# Qwiic_RFID_Tag_X01.net
KiCad netlist of a schematic drawn in EAGLE
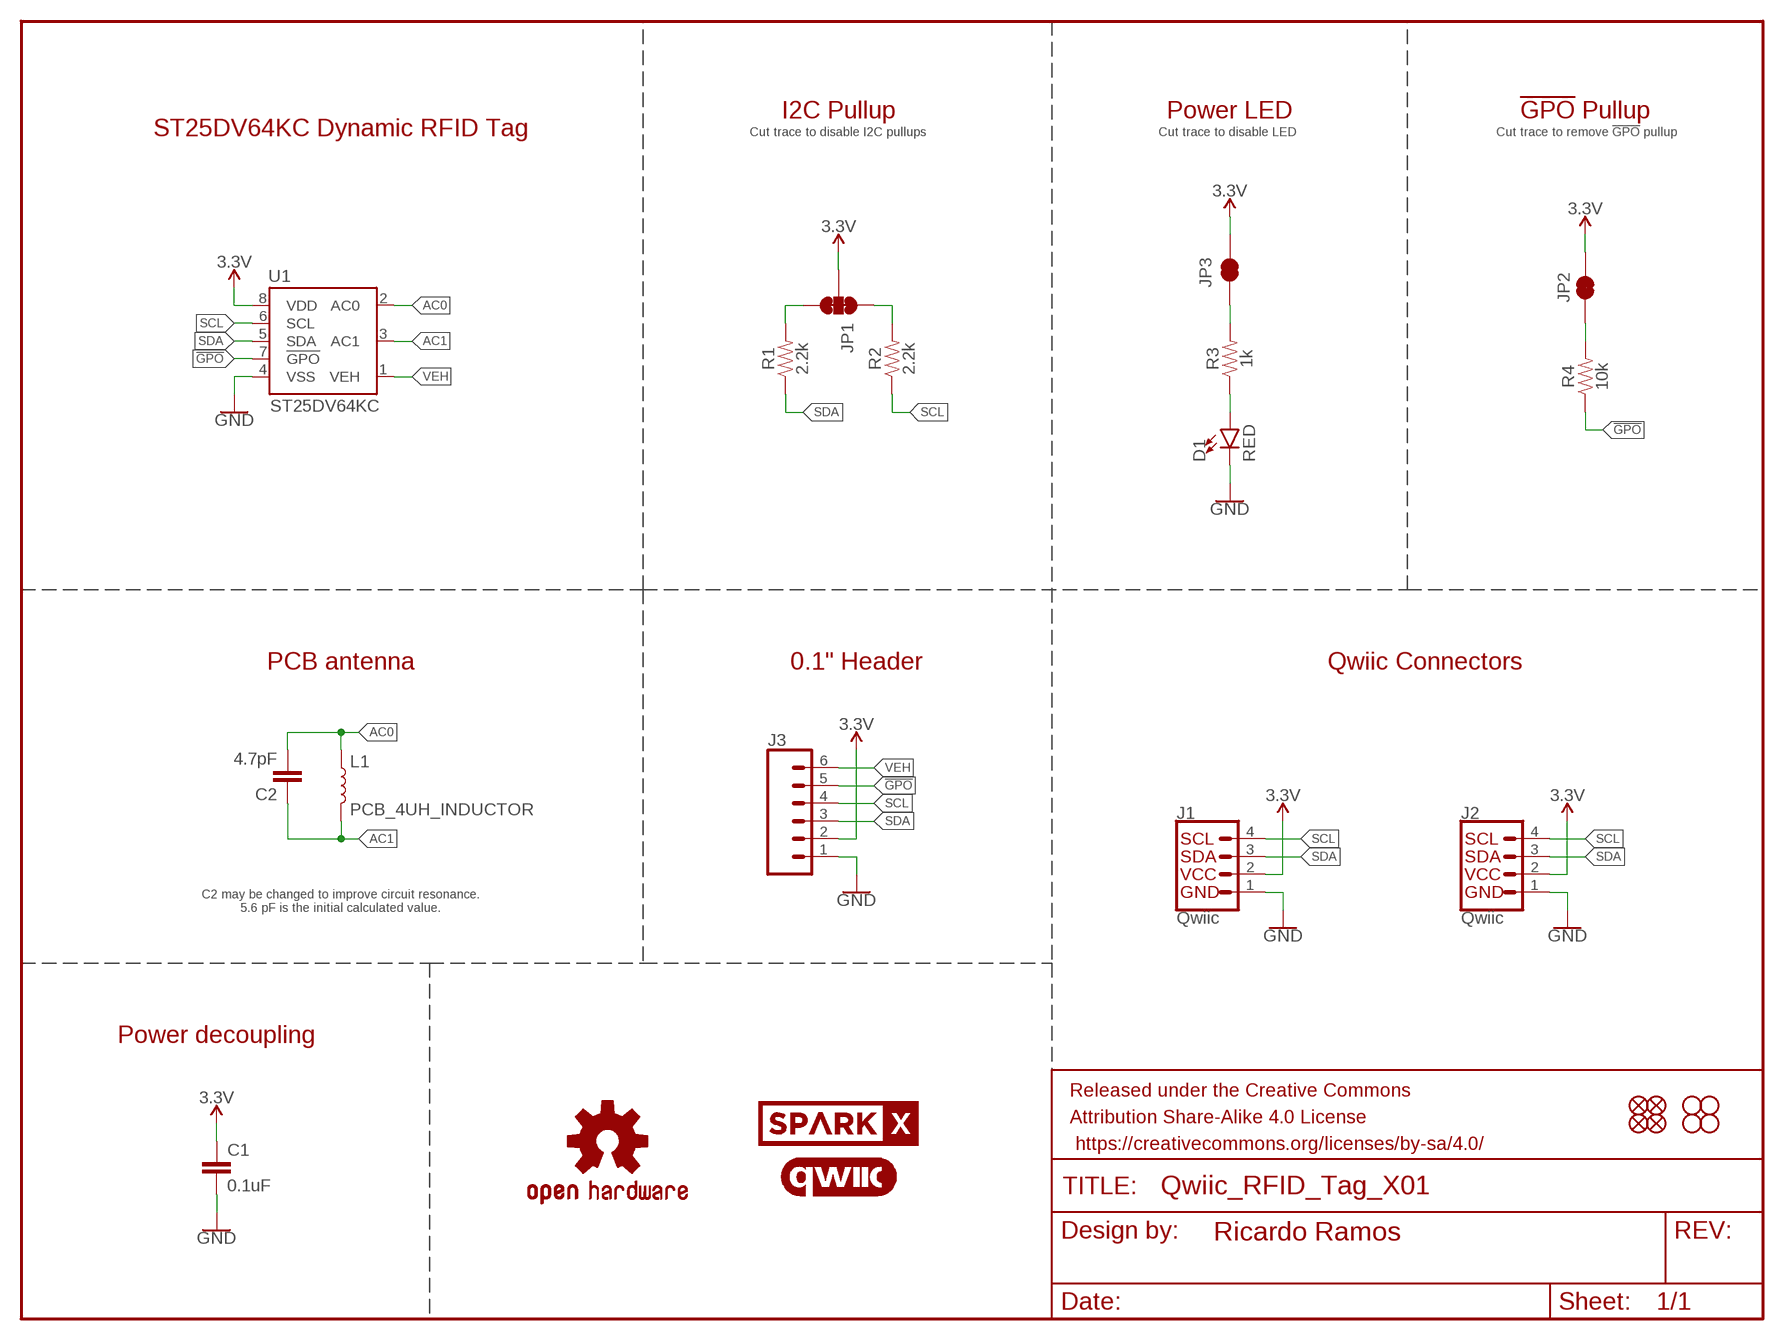
[diagram p0: schematic, sheet 1]

(export (version "E")
  (design (tool "Eeschema 10.0.6"))
  (components
    (comp (ref "C1")
      (value "0.1uF")
      (footprint "eagle-import:0603")
      (libsource (lib "eagle-import") (part "0.1UF-0603-25V-(+80/-20%)"))
    )
    (comp (ref "C2")
      (value "4.7pF")
      (footprint "eagle-import:0603")
      (libsource (lib "eagle-import") (part "4.7PF-0603-50V-5%"))
    )
    (comp (ref "D1")
      (value "RED")
      (footprint "eagle-import:LED-0603")
      (libsource (lib "eagle-import") (part "LED-RED0603"))
    )
    (comp (ref "FD1")
      (value "FIDUCIAL1X2")
      (footprint "eagle-import:FIDUCIAL-1X2")
      (libsource (lib "eagle-import") (part "FIDUCIAL1X2"))
    )
    (comp (ref "FD2")
      (value "FIDUCIAL1X2")
      (footprint "eagle-import:FIDUCIAL-1X2")
      (libsource (lib "eagle-import") (part "FIDUCIAL1X2"))
    )
    (comp (ref "FD3")
      (value "FIDUCIAL1X2")
      (footprint "eagle-import:FIDUCIAL-1X2")
      (libsource (lib "eagle-import") (part "FIDUCIAL1X2"))
    )
    (comp (ref "FD4")
      (value "FIDUCIAL1X2")
      (footprint "eagle-import:FIDUCIAL-1X2")
      (libsource (lib "eagle-import") (part "FIDUCIAL1X2"))
    )
    (comp (ref "FRAME1")
      (value "FRAME-LETTERNO_PACKAGE")
      (footprint "eagle-import:DUMMY")
      (fields (field (name "DESIGNER") "Ricardo Ramos") (field (name "DESIGNER_1") "Ricardo Ramos"))
      (libsource (lib "eagle-import") (part "FRAME-LETTERNO_PACKAGE"))
    )
    (comp (ref "H1")
      (value "STAND-OFF")
      (footprint "eagle-import:STAND-OFF")
      (libsource (lib "eagle-import") (part "STAND-OFF"))
    )
    (comp (ref "H2")
      (value "STAND-OFF")
      (footprint "eagle-import:STAND-OFF")
      (libsource (lib "eagle-import") (part "STAND-OFF"))
    )
    (comp (ref "H3")
      (value "STAND-OFF")
      (footprint "eagle-import:STAND-OFF")
      (libsource (lib "eagle-import") (part "STAND-OFF"))
    )
    (comp (ref "H4")
      (value "STAND-OFF")
      (footprint "eagle-import:STAND-OFF")
      (libsource (lib "eagle-import") (part "STAND-OFF"))
    )
    (comp (ref "J1")
      (value "Qwiic")
      (footprint "eagle-import:JST04_1MM_RA")
      (libsource (lib "eagle-import") (part "QWIIC_CONNECTORJS-1MM"))
    )
    (comp (ref "J2")
      (value "Qwiic")
      (footprint "eagle-import:JST04_1MM_RA")
      (libsource (lib "eagle-import") (part "QWIIC_CONNECTORJS-1MM"))
    )
    (comp (ref "J3")
      (value "CONN_06NO_SILK_FEMALE_PTH")
      (footprint "eagle-import:1X06_NO_SILK")
      (libsource (lib "eagle-import") (part "CONN_06NO_SILK_FEMALE_PTH"))
    )
    (comp (ref "JP1")
      (value "JUMPER-SMT_3_2-NC_TRACE_SILK")
      (footprint "eagle-import:SMT-JUMPER_3_2-NC_TRACE_SILK")
      (libsource (lib "eagle-import") (part "JUMPER-SMT_3_2-NC_TRACE_SILK"))
    )
    (comp (ref "JP2")
      (value "JUMPER-SMT_2_NC_TRACE_SILK")
      (footprint "eagle-import:SMT-JUMPER_2_NC_TRACE_SILK")
      (libsource (lib "eagle-import") (part "JUMPER-SMT_2_NC_TRACE_SILK"))
    )
    (comp (ref "JP3")
      (value "JUMPER-SMT_2_NC_TRACE_SILK")
      (footprint "eagle-import:SMT-JUMPER_2_NC_TRACE_SILK")
      (libsource (lib "eagle-import") (part "JUMPER-SMT_2_NC_TRACE_SILK"))
    )
    (comp (ref "L1")
      (value "PCB_4UH_INDUCTOR")
      (footprint "eagle-import:PCB_4UH_INDUCTOR")
      (libsource (lib "eagle-import") (part "PCB_4UH_INDUCTOR"))
    )
    (comp (ref "LOGO1")
      (value "OSHW-LOGOMINI")
      (footprint "eagle-import:OSHW-LOGO-MINI")
      (libsource (lib "eagle-import") (part "OSHW-LOGOMINI"))
    )
    (comp (ref "LOGO2")
      (value "QWIIC_LOGO_7MM")
      (footprint "eagle-import:QWIIC_7MM")
      (libsource (lib "eagle-import") (part "QWIIC_LOGO_7MM"))
    )
    (comp (ref "LOGO3")
      (value "QWIIC_LOGO_7MM")
      (footprint "eagle-import:QWIIC_7MM")
      (libsource (lib "eagle-import") (part "QWIIC_LOGO_7MM"))
    )
    (comp (ref "R1")
      (value "2.2k")
      (footprint "eagle-import:0603")
      (libsource (lib "eagle-import") (part "2.2KOHM-0603-1/10W-1%"))
    )
    (comp (ref "R2")
      (value "2.2k")
      (footprint "eagle-import:0603")
      (libsource (lib "eagle-import") (part "2.2KOHM-0603-1/10W-1%"))
    )
    (comp (ref "R3")
      (value "1k")
      (footprint "eagle-import:0603")
      (libsource (lib "eagle-import") (part "1KOHM-0603-1/10W-1%"))
    )
    (comp (ref "R4")
      (value "10k")
      (footprint "eagle-import:0603")
      (libsource (lib "eagle-import") (part "10KOHM-0603-1/10W-1%"))
    )
    (comp (ref "U$1")
      (value "SPARKX-LOGO5")
      (footprint "eagle-import:SPARKX-LARGE")
      (libsource (lib "eagle-import") (part "SPARKX-LOGO5"))
    )
    (comp (ref "U$2")
      (value "SPARKX-LOGO5")
      (footprint "eagle-import:SPARKX-LARGE")
      (libsource (lib "eagle-import") (part "SPARKX-LOGO5"))
    )
    (comp (ref "U1")
      (value "ST25DV64KC")
      (footprint "eagle-import:SO08")
      (libsource (lib "eagle-import") (part "ST25DV64KC"))
    )
  )
  (nets
    (net (code "1") (name "/~{GPO}") (class "Default")
      (node (ref "J3") (pin "5") (pinfunction "5_5") (pintype "passive"))
      (node (ref "R4") (pin "1") (pinfunction "1_1") (pintype "passive"))
      (node (ref "U1") (pin "7") (pinfunction "~{GPO}_7") (pintype "output"))
    )
    (net (code "2") (name "3.3V") (class "Default")
      (node (ref "C1") (pin "1") (pinfunction "1_1") (pintype "passive"))
      (node (ref "J1") (pin "2") (pinfunction "2_2") (pintype "power_in"))
      (node (ref "J2") (pin "2") (pinfunction "2_2") (pintype "power_in"))
      (node (ref "J3") (pin "2") (pinfunction "2_2") (pintype "passive"))
      (node (ref "JP1") (pin "2") (pinfunction "2_2") (pintype "passive"))
      (node (ref "JP2") (pin "2") (pinfunction "2_2") (pintype "passive"))
      (node (ref "JP3") (pin "2") (pinfunction "2_2") (pintype "passive"))
      (node (ref "U1") (pin "8") (pinfunction "VDD_8") (pintype "power_in"))
    )
    (net (code "3") (name "AC0") (class "Default")
      (node (ref "C2") (pin "2") (pinfunction "2_2") (pintype "passive"))
      (node (ref "L1") (pin "IN1") (pinfunction "1_IN1") (pintype "passive"))
      (node (ref "U1") (pin "2") (pinfunction "AC0_2") (pintype "bidirectional"))
    )
    (net (code "4") (name "AC1") (class "Default")
      (node (ref "C2") (pin "1") (pinfunction "1_1") (pintype "passive"))
      (node (ref "L1") (pin "IN2") (pinfunction "2_IN2") (pintype "passive"))
      (node (ref "U1") (pin "3") (pinfunction "AC1_3") (pintype "bidirectional"))
    )
    (net (code "5") (name "GND") (class "Default")
      (node (ref "C1") (pin "2") (pinfunction "2_2") (pintype "passive"))
      (node (ref "D1") (pin "C") (pinfunction "C_C") (pintype "passive"))
      (node (ref "J1") (pin "1") (pinfunction "1_1") (pintype "power_in"))
      (node (ref "J2") (pin "1") (pinfunction "1_1") (pintype "power_in"))
      (node (ref "J3") (pin "1") (pinfunction "1_1") (pintype "passive"))
      (node (ref "U1") (pin "4") (pinfunction "VSS_4") (pintype "power_in"))
    )
    (net (code "6") (name "Net-(D1-PadA)") (class "Default")
      (node (ref "D1") (pin "A") (pinfunction "A_A") (pintype "passive"))
      (node (ref "R3") (pin "1") (pinfunction "1_1") (pintype "passive"))
    )
    (net (code "7") (name "Net-(JP1-Pad1)") (class "Default")
      (node (ref "JP1") (pin "1") (pinfunction "1_1") (pintype "passive"))
      (node (ref "R2") (pin "2") (pinfunction "2_2") (pintype "passive"))
    )
    (net (code "8") (name "Net-(JP1-Pad3)") (class "Default")
      (node (ref "JP1") (pin "3") (pinfunction "3_3") (pintype "passive"))
      (node (ref "R1") (pin "2") (pinfunction "2_2") (pintype "passive"))
    )
    (net (code "9") (name "Net-(JP2-Pad1)") (class "Default")
      (node (ref "JP2") (pin "1") (pinfunction "1_1") (pintype "passive"))
      (node (ref "R4") (pin "2") (pinfunction "2_2") (pintype "passive"))
    )
    (net (code "10") (name "Net-(JP3-Pad1)") (class "Default")
      (node (ref "JP3") (pin "1") (pinfunction "1_1") (pintype "passive"))
      (node (ref "R3") (pin "2") (pinfunction "2_2") (pintype "passive"))
    )
    (net (code "11") (name "SCL") (class "Default")
      (node (ref "J1") (pin "4") (pinfunction "4_4") (pintype "passive"))
      (node (ref "J2") (pin "4") (pinfunction "4_4") (pintype "passive"))
      (node (ref "J3") (pin "4") (pinfunction "4_4") (pintype "passive"))
      (node (ref "R2") (pin "1") (pinfunction "1_1") (pintype "passive"))
      (node (ref "U1") (pin "6") (pinfunction "SCL_6") (pintype "bidirectional"))
    )
    (net (code "12") (name "SDA") (class "Default")
      (node (ref "J1") (pin "3") (pinfunction "3_3") (pintype "passive"))
      (node (ref "J2") (pin "3") (pinfunction "3_3") (pintype "passive"))
      (node (ref "J3") (pin "3") (pinfunction "3_3") (pintype "passive"))
      (node (ref "R1") (pin "1") (pinfunction "1_1") (pintype "passive"))
      (node (ref "U1") (pin "5") (pinfunction "SDA_5") (pintype "bidirectional"))
    )
    (net (code "13") (name "VEH") (class "Default")
      (node (ref "J3") (pin "6") (pinfunction "6_6") (pintype "passive"))
      (node (ref "U1") (pin "1") (pinfunction "VEH_1") (pintype "power_in"))
    )
  )
)
